# D_INPUT.net
KiCad netlist of a schematic drawn in Altium Designer
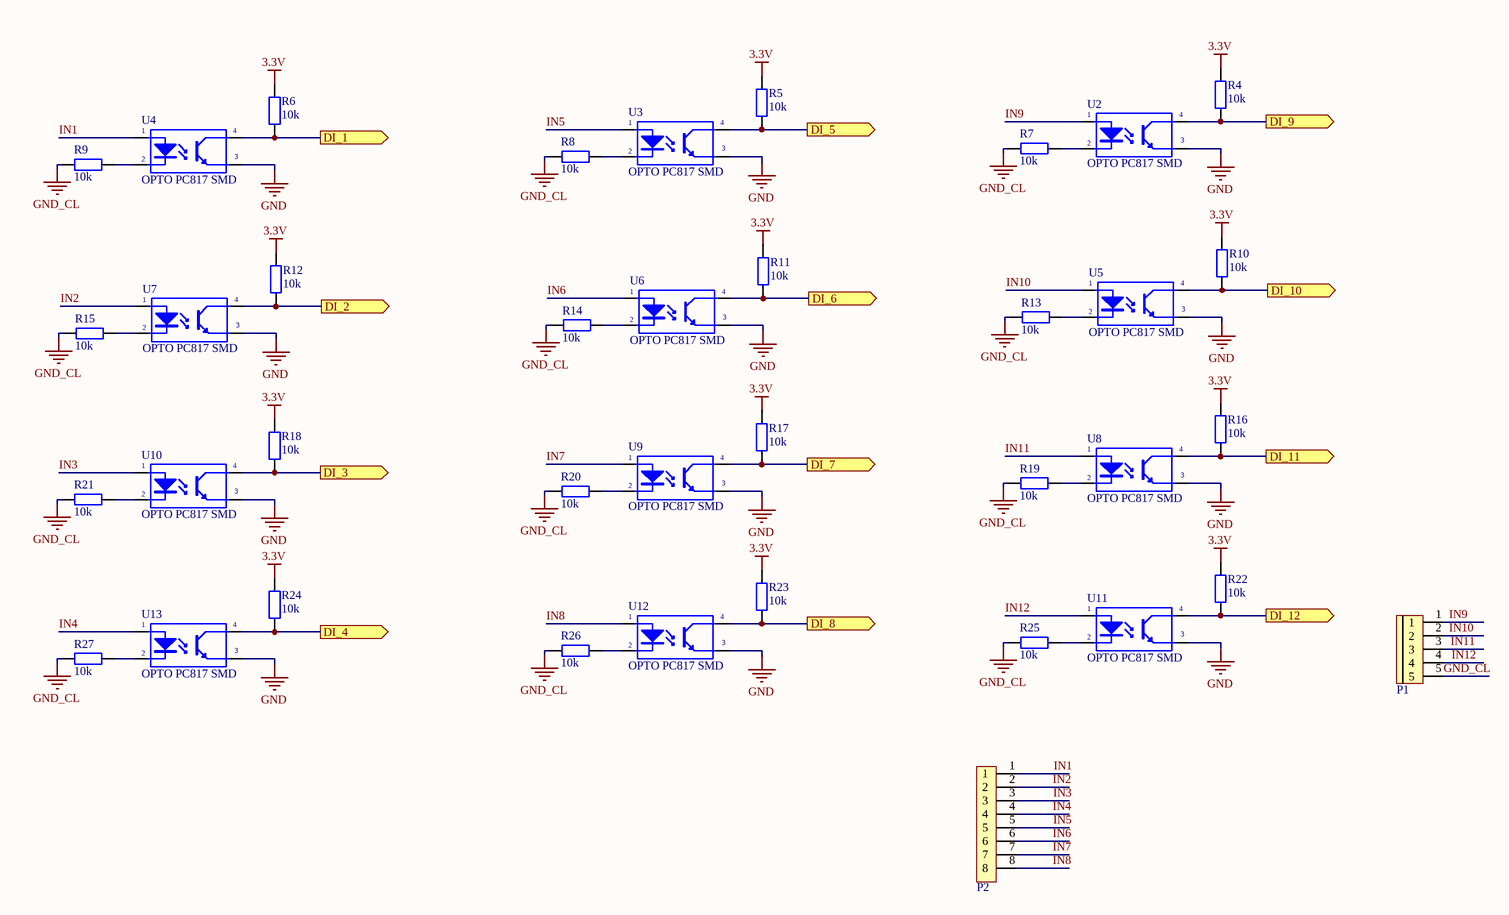
[diagram p0: D_INPUT.SchDoc]

(export (version "E")
  (design (tool "Eeschema 10.0.6"))
  (components
    (comp (ref "P1")
      (value "CON 5 EDG5.08")
      (footprint "CON 5 5EDG5.08")
      (description "Cắm")
      (libsource (lib "Altium_Lib_by_KhueNguyenCreator") (part "CON 5 EDG5.08"))
    )
    (comp (ref "P2")
      (value "CON 8 EDG5.08")
      (footprint "CON 8 8EDG5.08")
      (description "Cắm")
      (libsource (lib "Altium_Lib_by_KhueNguyenCreator") (part "CON 8 EDG5.08"))
    )
    (comp (ref "R4")
      (value "10k")
      (footprint "tro smd 0805")
      (description "Dán")
      (libsource (lib "Altium_Lib_by_KhueNguyenCreator") (part "Tro 0805 1% 10k"))
    )
    (comp (ref "R5")
      (value "10k")
      (footprint "tro smd 0805")
      (description "Dán")
      (libsource (lib "Altium_Lib_by_KhueNguyenCreator") (part "Tro 0805 1% 10k"))
    )
    (comp (ref "R6")
      (value "10k")
      (footprint "tro smd 0805")
      (description "Dán")
      (libsource (lib "Altium_Lib_by_KhueNguyenCreator") (part "Tro 0805 1% 10k"))
    )
    (comp (ref "R7")
      (value "10k")
      (footprint "tro smd 0805")
      (description "Dán")
      (libsource (lib "Altium_Lib_by_KhueNguyenCreator") (part "Tro 0805 1% 10k"))
    )
    (comp (ref "R8")
      (value "10k")
      (footprint "tro smd 0805")
      (description "Dán")
      (libsource (lib "Altium_Lib_by_KhueNguyenCreator") (part "Tro 0805 1% 10k"))
    )
    (comp (ref "R9")
      (value "10k")
      (footprint "tro smd 0805")
      (description "Dán")
      (libsource (lib "Altium_Lib_by_KhueNguyenCreator") (part "Tro 0805 1% 10k"))
    )
    (comp (ref "R10")
      (value "10k")
      (footprint "tro smd 0805")
      (description "Dán")
      (libsource (lib "Altium_Lib_by_KhueNguyenCreator") (part "Tro 0805 1% 10k"))
    )
    (comp (ref "R11")
      (value "10k")
      (footprint "tro smd 0805")
      (description "Dán")
      (libsource (lib "Altium_Lib_by_KhueNguyenCreator") (part "Tro 0805 1% 10k"))
    )
    (comp (ref "R12")
      (value "10k")
      (footprint "tro smd 0805")
      (description "Dán")
      (libsource (lib "Altium_Lib_by_KhueNguyenCreator") (part "Tro 0805 1% 10k"))
    )
    (comp (ref "R13")
      (value "10k")
      (footprint "tro smd 0805")
      (description "Dán")
      (libsource (lib "Altium_Lib_by_KhueNguyenCreator") (part "Tro 0805 1% 10k"))
    )
    (comp (ref "R14")
      (value "10k")
      (footprint "tro smd 0805")
      (description "Dán")
      (libsource (lib "Altium_Lib_by_KhueNguyenCreator") (part "Tro 0805 1% 10k"))
    )
    (comp (ref "R15")
      (value "10k")
      (footprint "tro smd 0805")
      (description "Dán")
      (libsource (lib "Altium_Lib_by_KhueNguyenCreator") (part "Tro 0805 1% 10k"))
    )
    (comp (ref "R16")
      (value "10k")
      (footprint "tro smd 0805")
      (description "Dán")
      (libsource (lib "Altium_Lib_by_KhueNguyenCreator") (part "Tro 0805 1% 10k"))
    )
    (comp (ref "R17")
      (value "10k")
      (footprint "tro smd 0805")
      (description "Dán")
      (libsource (lib "Altium_Lib_by_KhueNguyenCreator") (part "Tro 0805 1% 10k"))
    )
    (comp (ref "R18")
      (value "10k")
      (footprint "tro smd 0805")
      (description "Dán")
      (libsource (lib "Altium_Lib_by_KhueNguyenCreator") (part "Tro 0805 1% 10k"))
    )
    (comp (ref "R19")
      (value "10k")
      (footprint "tro smd 0805")
      (description "Dán")
      (libsource (lib "Altium_Lib_by_KhueNguyenCreator") (part "Tro 0805 1% 10k"))
    )
    (comp (ref "R20")
      (value "10k")
      (footprint "tro smd 0805")
      (description "Dán")
      (libsource (lib "Altium_Lib_by_KhueNguyenCreator") (part "Tro 0805 1% 10k"))
    )
    (comp (ref "R21")
      (value "10k")
      (footprint "tro smd 0805")
      (description "Dán")
      (libsource (lib "Altium_Lib_by_KhueNguyenCreator") (part "Tro 0805 1% 10k"))
    )
    (comp (ref "R22")
      (value "10k")
      (footprint "tro smd 0805")
      (description "Dán")
      (libsource (lib "Altium_Lib_by_KhueNguyenCreator") (part "Tro 0805 1% 10k"))
    )
    (comp (ref "R23")
      (value "10k")
      (footprint "tro smd 0805")
      (description "Dán")
      (libsource (lib "Altium_Lib_by_KhueNguyenCreator") (part "Tro 0805 1% 10k"))
    )
    (comp (ref "R24")
      (value "10k")
      (footprint "tro smd 0805")
      (description "Dán")
      (libsource (lib "Altium_Lib_by_KhueNguyenCreator") (part "Tro 0805 1% 10k"))
    )
    (comp (ref "R25")
      (value "10k")
      (footprint "tro smd 0805")
      (description "Dán")
      (libsource (lib "Altium_Lib_by_KhueNguyenCreator") (part "Tro 0805 1% 10k"))
    )
    (comp (ref "R26")
      (value "10k")
      (footprint "tro smd 0805")
      (description "Dán")
      (libsource (lib "Altium_Lib_by_KhueNguyenCreator") (part "Tro 0805 1% 10k"))
    )
    (comp (ref "R27")
      (value "10k")
      (footprint "tro smd 0805")
      (description "Dán")
      (libsource (lib "Altium_Lib_by_KhueNguyenCreator") (part "Tro 0805 1% 10k"))
    )
    (comp (ref "U2")
      (value "OPTO PC817 SMD")
      (footprint "SOP4")
      (description "Single Opto")
      (libsource (lib "Altium_Lib_by_KhueNguyenCreator") (part "OPTO PC817 SMD"))
    )
    (comp (ref "U3")
      (value "OPTO PC817 SMD")
      (footprint "SOP4")
      (description "Single Opto")
      (libsource (lib "Altium_Lib_by_KhueNguyenCreator") (part "OPTO PC817 SMD"))
    )
    (comp (ref "U4")
      (value "OPTO PC817 SMD")
      (footprint "SOP4")
      (description "Single Opto")
      (libsource (lib "Altium_Lib_by_KhueNguyenCreator") (part "OPTO PC817 SMD"))
    )
    (comp (ref "U5")
      (value "OPTO PC817 SMD")
      (footprint "SOP4")
      (description "Single Opto")
      (libsource (lib "Altium_Lib_by_KhueNguyenCreator") (part "OPTO PC817 SMD"))
    )
    (comp (ref "U6")
      (value "OPTO PC817 SMD")
      (footprint "SOP4")
      (description "Single Opto")
      (libsource (lib "Altium_Lib_by_KhueNguyenCreator") (part "OPTO PC817 SMD"))
    )
    (comp (ref "U7")
      (value "OPTO PC817 SMD")
      (footprint "SOP4")
      (description "Single Opto")
      (libsource (lib "Altium_Lib_by_KhueNguyenCreator") (part "OPTO PC817 SMD"))
    )
    (comp (ref "U8")
      (value "OPTO PC817 SMD")
      (footprint "SOP4")
      (description "Single Opto")
      (libsource (lib "Altium_Lib_by_KhueNguyenCreator") (part "OPTO PC817 SMD"))
    )
    (comp (ref "U9")
      (value "OPTO PC817 SMD")
      (footprint "SOP4")
      (description "Single Opto")
      (libsource (lib "Altium_Lib_by_KhueNguyenCreator") (part "OPTO PC817 SMD"))
    )
    (comp (ref "U10")
      (value "OPTO PC817 SMD")
      (footprint "SOP4")
      (description "Single Opto")
      (libsource (lib "Altium_Lib_by_KhueNguyenCreator") (part "OPTO PC817 SMD"))
    )
    (comp (ref "U11")
      (value "OPTO PC817 SMD")
      (footprint "SOP4")
      (description "Single Opto")
      (libsource (lib "Altium_Lib_by_KhueNguyenCreator") (part "OPTO PC817 SMD"))
    )
    (comp (ref "U12")
      (value "OPTO PC817 SMD")
      (footprint "SOP4")
      (description "Single Opto")
      (libsource (lib "Altium_Lib_by_KhueNguyenCreator") (part "OPTO PC817 SMD"))
    )
    (comp (ref "U13")
      (value "OPTO PC817 SMD")
      (footprint "SOP4")
      (description "Single Opto")
      (libsource (lib "Altium_Lib_by_KhueNguyenCreator") (part "OPTO PC817 SMD"))
    )
  )
  (nets
    (net (code "1") (name "/DI_1") (class "Default")
      (node (ref "R6") (pin "2") (pinfunction "2_2") (pintype "passive"))
      (node (ref "U4") (pin "4") (pinfunction "C_4") (pintype "passive"))
    )
    (net (code "2") (name "/DI_2") (class "Default")
      (node (ref "R12") (pin "2") (pinfunction "2_2") (pintype "passive"))
      (node (ref "U7") (pin "4") (pinfunction "C_4") (pintype "passive"))
    )
    (net (code "3") (name "/DI_3") (class "Default")
      (node (ref "R18") (pin "2") (pinfunction "2_2") (pintype "passive"))
      (node (ref "U10") (pin "4") (pinfunction "C_4") (pintype "passive"))
    )
    (net (code "4") (name "/DI_4") (class "Default")
      (node (ref "R24") (pin "2") (pinfunction "2_2") (pintype "passive"))
      (node (ref "U13") (pin "4") (pinfunction "C_4") (pintype "passive"))
    )
    (net (code "5") (name "/DI_5") (class "Default")
      (node (ref "R5") (pin "2") (pinfunction "2_2") (pintype "passive"))
      (node (ref "U3") (pin "4") (pinfunction "C_4") (pintype "passive"))
    )
    (net (code "6") (name "/DI_6") (class "Default")
      (node (ref "R11") (pin "2") (pinfunction "2_2") (pintype "passive"))
      (node (ref "U6") (pin "4") (pinfunction "C_4") (pintype "passive"))
    )
    (net (code "7") (name "/DI_7") (class "Default")
      (node (ref "R17") (pin "2") (pinfunction "2_2") (pintype "passive"))
      (node (ref "U9") (pin "4") (pinfunction "C_4") (pintype "passive"))
    )
    (net (code "8") (name "/DI_8") (class "Default")
      (node (ref "R23") (pin "2") (pinfunction "2_2") (pintype "passive"))
      (node (ref "U12") (pin "4") (pinfunction "C_4") (pintype "passive"))
    )
    (net (code "9") (name "/DI_9") (class "Default")
      (node (ref "R4") (pin "2") (pinfunction "2_2") (pintype "passive"))
      (node (ref "U2") (pin "4") (pinfunction "C_4") (pintype "passive"))
    )
    (net (code "10") (name "/DI_10") (class "Default")
      (node (ref "R10") (pin "2") (pinfunction "2_2") (pintype "passive"))
      (node (ref "U5") (pin "4") (pinfunction "C_4") (pintype "passive"))
    )
    (net (code "11") (name "/DI_11") (class "Default")
      (node (ref "R16") (pin "2") (pinfunction "2_2") (pintype "passive"))
      (node (ref "U8") (pin "4") (pinfunction "C_4") (pintype "passive"))
    )
    (net (code "12") (name "/DI_12") (class "Default")
      (node (ref "R22") (pin "2") (pinfunction "2_2") (pintype "passive"))
      (node (ref "U11") (pin "4") (pinfunction "C_4") (pintype "passive"))
    )
    (net (code "13") (name "/IN1") (class "Default")
      (node (ref "P2") (pin "1") (pinfunction "1_1") (pintype "passive"))
      (node (ref "U4") (pin "1") (pinfunction "A_1") (pintype "passive"))
    )
    (net (code "14") (name "/IN2") (class "Default")
      (node (ref "P2") (pin "2") (pinfunction "2_2") (pintype "passive"))
      (node (ref "U7") (pin "1") (pinfunction "A_1") (pintype "passive"))
    )
    (net (code "15") (name "/IN3") (class "Default")
      (node (ref "P2") (pin "3") (pinfunction "3_3") (pintype "passive"))
      (node (ref "U10") (pin "1") (pinfunction "A_1") (pintype "passive"))
    )
    (net (code "16") (name "/IN4") (class "Default")
      (node (ref "P2") (pin "4") (pinfunction "4_4") (pintype "passive"))
      (node (ref "U13") (pin "1") (pinfunction "A_1") (pintype "passive"))
    )
    (net (code "17") (name "/IN5") (class "Default")
      (node (ref "P2") (pin "5") (pinfunction "5_5") (pintype "passive"))
      (node (ref "U3") (pin "1") (pinfunction "A_1") (pintype "passive"))
    )
    (net (code "18") (name "/IN6") (class "Default")
      (node (ref "P2") (pin "6") (pinfunction "6_6") (pintype "passive"))
      (node (ref "U6") (pin "1") (pinfunction "A_1") (pintype "passive"))
    )
    (net (code "19") (name "/IN7") (class "Default")
      (node (ref "P2") (pin "7") (pinfunction "7_7") (pintype "passive"))
      (node (ref "U9") (pin "1") (pinfunction "A_1") (pintype "passive"))
    )
    (net (code "20") (name "/IN8") (class "Default")
      (node (ref "P2") (pin "8") (pinfunction "8_8") (pintype "passive"))
      (node (ref "U12") (pin "1") (pinfunction "A_1") (pintype "passive"))
    )
    (net (code "21") (name "/IN9") (class "Default")
      (node (ref "P1") (pin "1") (pinfunction "1_1") (pintype "passive"))
      (node (ref "U2") (pin "1") (pinfunction "A_1") (pintype "passive"))
    )
    (net (code "22") (name "/IN10") (class "Default")
      (node (ref "P1") (pin "2") (pinfunction "2_2") (pintype "passive"))
      (node (ref "U5") (pin "1") (pinfunction "A_1") (pintype "passive"))
    )
    (net (code "23") (name "/IN11") (class "Default")
      (node (ref "P1") (pin "3") (pinfunction "3_3") (pintype "passive"))
      (node (ref "U8") (pin "1") (pinfunction "A_1") (pintype "passive"))
    )
    (net (code "24") (name "/IN12") (class "Default")
      (node (ref "P1") (pin "4") (pinfunction "4_4") (pintype "passive"))
      (node (ref "U11") (pin "1") (pinfunction "A_1") (pintype "passive"))
    )
    (net (code "25") (name "3.3V") (class "Default")
      (node (ref "R10") (pin "1") (pinfunction "1_1") (pintype "passive"))
      (node (ref "R11") (pin "1") (pinfunction "1_1") (pintype "passive"))
      (node (ref "R12") (pin "1") (pinfunction "1_1") (pintype "passive"))
      (node (ref "R16") (pin "1") (pinfunction "1_1") (pintype "passive"))
      (node (ref "R17") (pin "1") (pinfunction "1_1") (pintype "passive"))
      (node (ref "R18") (pin "1") (pinfunction "1_1") (pintype "passive"))
      (node (ref "R22") (pin "1") (pinfunction "1_1") (pintype "passive"))
      (node (ref "R23") (pin "1") (pinfunction "1_1") (pintype "passive"))
      (node (ref "R24") (pin "1") (pinfunction "1_1") (pintype "passive"))
      (node (ref "R4") (pin "1") (pinfunction "1_1") (pintype "passive"))
      (node (ref "R5") (pin "1") (pinfunction "1_1") (pintype "passive"))
      (node (ref "R6") (pin "1") (pinfunction "1_1") (pintype "passive"))
    )
    (net (code "26") (name "GND") (class "Default")
      (node (ref "U10") (pin "3") (pinfunction "E_3") (pintype "passive"))
      (node (ref "U11") (pin "3") (pinfunction "E_3") (pintype "passive"))
      (node (ref "U12") (pin "3") (pinfunction "E_3") (pintype "passive"))
      (node (ref "U13") (pin "3") (pinfunction "E_3") (pintype "passive"))
      (node (ref "U2") (pin "3") (pinfunction "E_3") (pintype "passive"))
      (node (ref "U3") (pin "3") (pinfunction "E_3") (pintype "passive"))
      (node (ref "U4") (pin "3") (pinfunction "E_3") (pintype "passive"))
      (node (ref "U5") (pin "3") (pinfunction "E_3") (pintype "passive"))
      (node (ref "U6") (pin "3") (pinfunction "E_3") (pintype "passive"))
      (node (ref "U7") (pin "3") (pinfunction "E_3") (pintype "passive"))
      (node (ref "U8") (pin "3") (pinfunction "E_3") (pintype "passive"))
      (node (ref "U9") (pin "3") (pinfunction "E_3") (pintype "passive"))
    )
    (net (code "27") (name "GND_CL") (class "Default")
      (node (ref "P1") (pin "5") (pinfunction "5_5") (pintype "passive"))
      (node (ref "R13") (pin "2") (pinfunction "2_2") (pintype "passive"))
      (node (ref "R14") (pin "2") (pinfunction "2_2") (pintype "passive"))
      (node (ref "R15") (pin "2") (pinfunction "2_2") (pintype "passive"))
      (node (ref "R19") (pin "2") (pinfunction "2_2") (pintype "passive"))
      (node (ref "R20") (pin "2") (pinfunction "2_2") (pintype "passive"))
      (node (ref "R21") (pin "2") (pinfunction "2_2") (pintype "passive"))
      (node (ref "R25") (pin "2") (pinfunction "2_2") (pintype "passive"))
      (node (ref "R26") (pin "2") (pinfunction "2_2") (pintype "passive"))
      (node (ref "R27") (pin "2") (pinfunction "2_2") (pintype "passive"))
      (node (ref "R7") (pin "2") (pinfunction "2_2") (pintype "passive"))
      (node (ref "R8") (pin "2") (pinfunction "2_2") (pintype "passive"))
      (node (ref "R9") (pin "2") (pinfunction "2_2") (pintype "passive"))
    )
    (net (code "28") (name "Net-(U2-K)") (class "Default")
      (node (ref "R7") (pin "1") (pinfunction "1_1") (pintype "passive"))
      (node (ref "U2") (pin "2") (pinfunction "K_2") (pintype "passive"))
    )
    (net (code "29") (name "Net-(U3-K)") (class "Default")
      (node (ref "R8") (pin "1") (pinfunction "1_1") (pintype "passive"))
      (node (ref "U3") (pin "2") (pinfunction "K_2") (pintype "passive"))
    )
    (net (code "30") (name "Net-(U4-K)") (class "Default")
      (node (ref "R9") (pin "1") (pinfunction "1_1") (pintype "passive"))
      (node (ref "U4") (pin "2") (pinfunction "K_2") (pintype "passive"))
    )
    (net (code "31") (name "Net-(U5-K)") (class "Default")
      (node (ref "R13") (pin "1") (pinfunction "1_1") (pintype "passive"))
      (node (ref "U5") (pin "2") (pinfunction "K_2") (pintype "passive"))
    )
    (net (code "32") (name "Net-(U6-K)") (class "Default")
      (node (ref "R14") (pin "1") (pinfunction "1_1") (pintype "passive"))
      (node (ref "U6") (pin "2") (pinfunction "K_2") (pintype "passive"))
    )
    (net (code "33") (name "Net-(U7-K)") (class "Default")
      (node (ref "R15") (pin "1") (pinfunction "1_1") (pintype "passive"))
      (node (ref "U7") (pin "2") (pinfunction "K_2") (pintype "passive"))
    )
    (net (code "34") (name "Net-(U8-K)") (class "Default")
      (node (ref "R19") (pin "1") (pinfunction "1_1") (pintype "passive"))
      (node (ref "U8") (pin "2") (pinfunction "K_2") (pintype "passive"))
    )
    (net (code "35") (name "Net-(U9-K)") (class "Default")
      (node (ref "R20") (pin "1") (pinfunction "1_1") (pintype "passive"))
      (node (ref "U9") (pin "2") (pinfunction "K_2") (pintype "passive"))
    )
    (net (code "36") (name "Net-(U10-K)") (class "Default")
      (node (ref "R21") (pin "1") (pinfunction "1_1") (pintype "passive"))
      (node (ref "U10") (pin "2") (pinfunction "K_2") (pintype "passive"))
    )
    (net (code "37") (name "Net-(U11-K)") (class "Default")
      (node (ref "R25") (pin "1") (pinfunction "1_1") (pintype "passive"))
      (node (ref "U11") (pin "2") (pinfunction "K_2") (pintype "passive"))
    )
    (net (code "38") (name "Net-(U12-K)") (class "Default")
      (node (ref "R26") (pin "1") (pinfunction "1_1") (pintype "passive"))
      (node (ref "U12") (pin "2") (pinfunction "K_2") (pintype "passive"))
    )
    (net (code "39") (name "Net-(U13-K)") (class "Default")
      (node (ref "R27") (pin "1") (pinfunction "1_1") (pintype "passive"))
      (node (ref "U13") (pin "2") (pinfunction "K_2") (pintype "passive"))
    )
  )
)
